# HLK-V20-KIT-V2_1.net
KiCad netlist of a schematic drawn in Altium Designer
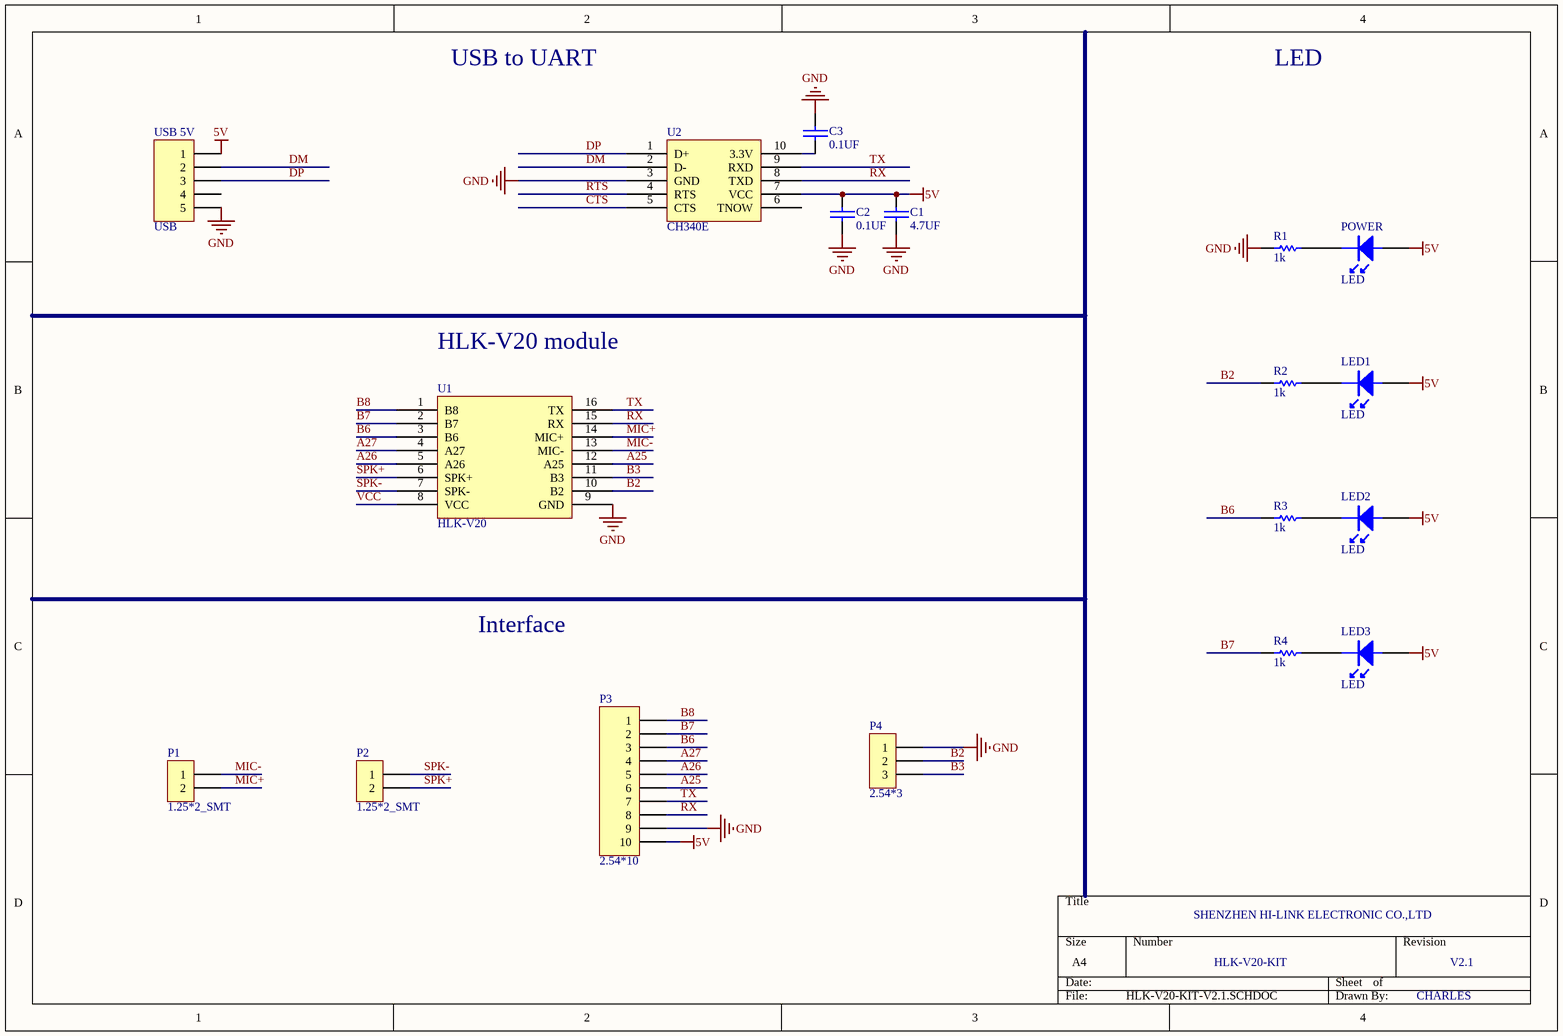
[diagram p0: HLK-V20-KIT-V2.1.SCHDOC]

(export (version "E")
  (design (tool "Eeschema 10.0.6"))
  (components
    (comp (ref "C1") (value "4.7UF") (description "Capacitor") (libsource (lib "*") (part "CAP")))
    (comp (ref "C2") (value "0.1UF") (description "Capacitor") (libsource (lib "*") (part "CAP")))
    (comp (ref "C3") (value "0.1UF") (description "Capacitor") (libsource (lib "*") (part "CAP")))
    (comp (ref "LED1")
      (value "LED")
      (footprint "0603LED")
      (libsource (lib "Miscellaneous Devices") (part "LED"))
    )
    (comp (ref "LED2")
      (value "LED")
      (footprint "0603LED")
      (libsource (lib "Miscellaneous Devices") (part "LED"))
    )
    (comp (ref "LED3")
      (value "LED")
      (footprint "0603LED")
      (libsource (lib "Miscellaneous Devices") (part "LED"))
    )
    (comp (ref "P1") (value "1.25*2_SMT") (description "Connector") (libsource (lib "插件") (part "CON2")))
    (comp (ref "P2") (value "1.25*2_SMT") (description "Connector") (libsource (lib "插件") (part "CON2")))
    (comp (ref "P3")
      (value "2.54*10")
      (footprint "HDR1X10")
      (description "Header, 10-Pin")
      (fields (field (name "PUBLISHER") "Altium Limited"))
      (libsource (lib "Miscellaneous Connectors") (part "Header 10"))
    )
    (comp (ref "P4") (value "2.54*3") (description "Connector") (libsource (lib "插件") (part "CON3")))
    (comp (ref "POWER")
      (value "LED")
      (footprint "0603LED")
      (libsource (lib "Miscellaneous Devices") (part "LED"))
    )
    (comp (ref "R1")
      (value "1k")
      (footprint "0603")
      (description "Resistor")
      (fields (field (name "Comment") "Res1") (field (name "PUBLISHER") "Altium Limited"))
      (libsource (lib "Miscellaneous Devices") (part "Res1"))
    )
    (comp (ref "R2")
      (value "1k")
      (footprint "0603")
      (description "Resistor")
      (fields (field (name "Comment") "Res1") (field (name "PUBLISHER") "Altium Limited"))
      (libsource (lib "Miscellaneous Devices") (part "Res1"))
    )
    (comp (ref "R3")
      (value "1k")
      (footprint "0603")
      (description "Resistor")
      (fields (field (name "Comment") "Res1") (field (name "PUBLISHER") "Altium Limited"))
      (libsource (lib "Miscellaneous Devices") (part "Res1"))
    )
    (comp (ref "R4")
      (value "1k")
      (footprint "0603")
      (description "Resistor")
      (fields (field (name "Comment") "Res1") (field (name "PUBLISHER") "Altium Limited"))
      (libsource (lib "Miscellaneous Devices") (part "Res1"))
    )
    (comp (ref "U1")
      (value "HLK-V20")
      (footprint "HLK-V20")
      (description "HLK-V20语音模块")
      (libsource (lib "HLK-V20原理图封装（AD9格式）") (part "HLK-V20"))
    )
    (comp (ref "U2") (value "CH340E") (footprint "MSOP-10") (libsource (lib "Schlib1") (part "CH340E")))
    (comp (ref "USB 5V")
      (value "USB")
      (footprint "MICRO_USB")
      (description "Header, 5-Pin")
      (fields (field (name "PUBLISHER") "Altium Limited"))
      (libsource (lib "Miscellaneous Connectors") (part "Header 5"))
    )
  )
  (nets
    (net (code "1") (name "/A25") (class "Default")
      (node (ref "P3") (pin "6") (pinfunction "6_6") (pintype "passive"))
      (node (ref "U1") (pin "12") (pinfunction "A25_12") (pintype "passive"))
    )
    (net (code "2") (name "/A26") (class "Default")
      (node (ref "P3") (pin "5") (pinfunction "5_5") (pintype "passive"))
      (node (ref "U1") (pin "5") (pinfunction "A26_5") (pintype "passive"))
    )
    (net (code "3") (name "/A27") (class "Default")
      (node (ref "P3") (pin "4") (pinfunction "4_4") (pintype "passive"))
      (node (ref "U1") (pin "4") (pinfunction "A27_4") (pintype "passive"))
    )
    (net (code "4") (name "/B2") (class "Default")
      (node (ref "P4") (pin "2") (pinfunction "2_2") (pintype "passive"))
      (node (ref "R2") (pin "2") (pinfunction "2_2") (pintype "passive"))
      (node (ref "U1") (pin "10") (pinfunction "B2_10") (pintype "passive"))
    )
    (net (code "5") (name "/B3") (class "Default")
      (node (ref "P4") (pin "3") (pinfunction "3_3") (pintype "passive"))
      (node (ref "U1") (pin "11") (pinfunction "B3_11") (pintype "passive"))
    )
    (net (code "6") (name "/B6") (class "Default")
      (node (ref "P3") (pin "3") (pinfunction "3_3") (pintype "passive"))
      (node (ref "R3") (pin "2") (pinfunction "2_2") (pintype "passive"))
      (node (ref "U1") (pin "3") (pinfunction "B6_3") (pintype "passive"))
    )
    (net (code "7") (name "/B7") (class "Default")
      (node (ref "P3") (pin "2") (pinfunction "2_2") (pintype "passive"))
      (node (ref "R4") (pin "2") (pinfunction "2_2") (pintype "passive"))
      (node (ref "U1") (pin "2") (pinfunction "B7_2") (pintype "passive"))
    )
    (net (code "8") (name "/B8") (class "Default")
      (node (ref "P3") (pin "1") (pinfunction "1_1") (pintype "passive"))
      (node (ref "U1") (pin "1") (pinfunction "B8_1") (pintype "passive"))
    )
    (net (code "9") (name "/CTS") (class "Default")
      (node (ref "U2") (pin "5") (pinfunction "CTS_5") (pintype "passive"))
    )
    (net (code "10") (name "/DM") (class "Default")
      (node (ref "U2") (pin "2") (pinfunction "D-_2") (pintype "passive"))
      (node (ref "USB 5V") (pin "2") (pinfunction "2_2") (pintype "passive"))
    )
    (net (code "11") (name "/DP") (class "Default")
      (node (ref "U2") (pin "1") (pinfunction "D+_1") (pintype "passive"))
      (node (ref "USB 5V") (pin "3") (pinfunction "3_3") (pintype "passive"))
    )
    (net (code "12") (name "/MIC+") (class "Default")
      (node (ref "P1") (pin "2") (pinfunction "2_2") (pintype "passive"))
      (node (ref "U1") (pin "14") (pinfunction "MIC+_14") (pintype "passive"))
    )
    (net (code "13") (name "/MIC-") (class "Default")
      (node (ref "P1") (pin "1") (pinfunction "1_1") (pintype "passive"))
      (node (ref "U1") (pin "13") (pinfunction "MIC-_13") (pintype "passive"))
    )
    (net (code "14") (name "/RTS") (class "Default")
      (node (ref "U2") (pin "4") (pinfunction "RTS_4") (pintype "passive"))
    )
    (net (code "15") (name "/RX") (class "Default")
      (node (ref "P3") (pin "8") (pinfunction "8_8") (pintype "passive"))
      (node (ref "U1") (pin "15") (pinfunction "RX_15") (pintype "passive"))
      (node (ref "U2") (pin "8") (pinfunction "TXD_8") (pintype "passive"))
    )
    (net (code "16") (name "/SPK+") (class "Default")
      (node (ref "P2") (pin "2") (pinfunction "2_2") (pintype "passive"))
      (node (ref "U1") (pin "6") (pinfunction "SPK+_6") (pintype "passive"))
    )
    (net (code "17") (name "/SPK-") (class "Default")
      (node (ref "P2") (pin "1") (pinfunction "1_1") (pintype "passive"))
      (node (ref "U1") (pin "7") (pinfunction "SPK-_7") (pintype "passive"))
    )
    (net (code "18") (name "/TX") (class "Default")
      (node (ref "P3") (pin "7") (pinfunction "7_7") (pintype "passive"))
      (node (ref "U1") (pin "16") (pinfunction "TX_16") (pintype "passive"))
      (node (ref "U2") (pin "9") (pinfunction "RXD_9") (pintype "passive"))
    )
    (net (code "19") (name "/VCC") (class "Default")
      (node (ref "U1") (pin "8") (pinfunction "VCC_8") (pintype "passive"))
    )
    (net (code "20") (name "5V") (class "Default")
      (node (ref "C1") (pin "2") (pinfunction "2_2") (pintype "passive"))
      (node (ref "C2") (pin "2") (pinfunction "2_2") (pintype "passive"))
      (node (ref "LED1") (pin "1") (pinfunction "1_1") (pintype "passive"))
      (node (ref "LED2") (pin "1") (pinfunction "1_1") (pintype "passive"))
      (node (ref "LED3") (pin "1") (pinfunction "1_1") (pintype "passive"))
      (node (ref "P3") (pin "10") (pinfunction "10_10") (pintype "passive"))
      (node (ref "POWER") (pin "1") (pinfunction "1_1") (pintype "passive"))
      (node (ref "U2") (pin "7") (pinfunction "VCC_7") (pintype "passive"))
      (node (ref "USB 5V") (pin "1") (pinfunction "1_1") (pintype "passive"))
    )
    (net (code "21") (name "GND") (class "Default")
      (node (ref "C1") (pin "1") (pinfunction "1_1") (pintype "passive"))
      (node (ref "C2") (pin "1") (pinfunction "1_1") (pintype "passive"))
      (node (ref "C3") (pin "1") (pinfunction "1_1") (pintype "passive"))
      (node (ref "P3") (pin "9") (pinfunction "9_9") (pintype "passive"))
      (node (ref "P4") (pin "1") (pinfunction "1_1") (pintype "passive"))
      (node (ref "R1") (pin "2") (pinfunction "2_2") (pintype "passive"))
      (node (ref "U1") (pin "9") (pinfunction "GND_9") (pintype "passive"))
      (node (ref "U2") (pin "3") (pinfunction "GND_3") (pintype "passive"))
      (node (ref "USB 5V") (pin "5") (pinfunction "5_5") (pintype "passive"))
    )
    (net (code "22") (name "Net-(LED1-Pad2)") (class "Default")
      (node (ref "LED1") (pin "2") (pinfunction "2_2") (pintype "passive"))
      (node (ref "R2") (pin "1") (pinfunction "1_1") (pintype "passive"))
    )
    (net (code "23") (name "Net-(LED2-Pad2)") (class "Default")
      (node (ref "LED2") (pin "2") (pinfunction "2_2") (pintype "passive"))
      (node (ref "R3") (pin "1") (pinfunction "1_1") (pintype "passive"))
    )
    (net (code "24") (name "Net-(LED3-Pad2)") (class "Default")
      (node (ref "LED3") (pin "2") (pinfunction "2_2") (pintype "passive"))
      (node (ref "R4") (pin "1") (pinfunction "1_1") (pintype "passive"))
    )
    (net (code "25") (name "Net-(POWER-Pad2)") (class "Default")
      (node (ref "POWER") (pin "2") (pinfunction "2_2") (pintype "passive"))
      (node (ref "R1") (pin "1") (pinfunction "1_1") (pintype "passive"))
    )
    (net (code "26") (name "Net-(U2-3.3V)") (class "Default")
      (node (ref "C3") (pin "2") (pinfunction "2_2") (pintype "passive"))
      (node (ref "U2") (pin "10") (pinfunction "3.3V_10") (pintype "passive"))
    )
    (net (code "27") (name "unconnected-(U2-TNOW-Pad6)") (class "Default")
      (node (ref "U2") (pin "6") (pinfunction "TNOW_6") (pintype "passive"))
    )
    (net (code "28") (name "unconnected-(USB 5V-Pad4)") (class "Default")
      (node (ref "USB 5V") (pin "4") (pinfunction "4_4") (pintype "passive"))
    )
  )
)
